# Spring2020.net
KiCad netlist of a schematic drawn in EAGLE
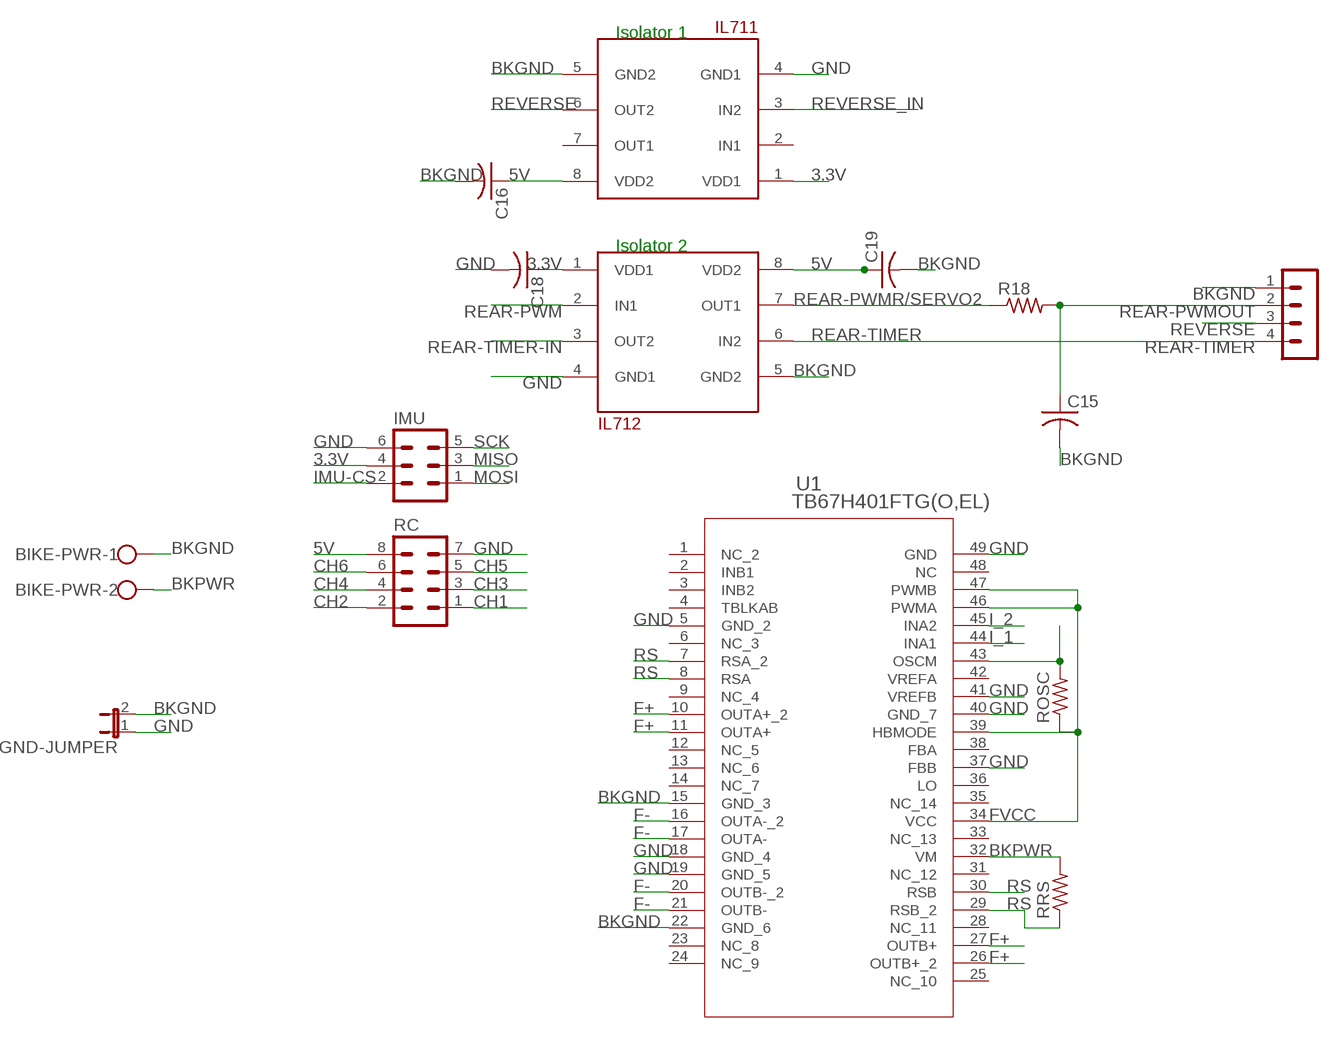
[diagram p0: schematic, sheet 1]

(export (version "E")
  (design (tool "Eeschema 10.0.6"))
  (components
    (comp (ref "BIKE-PWR")
      (value "W237-102")
      (footprint "eagle-import:W237-102")
      (fields (field (name "MPN") "237-102"))
      (libsource (lib "eagle-import") (part "W237-102"))
    )
    (comp (ref "C15")
      (value "C-US025-050X050")
      (footprint "eagle-import:C025-050X050")
      (libsource (lib "eagle-import") (part "C-US025-050X050"))
    )
    (comp (ref "C16")
      (value "C-US025-050X050")
      (footprint "eagle-import:C025-050X050")
      (libsource (lib "eagle-import") (part "C-US025-050X050"))
    )
    (comp (ref "C18")
      (value "C-US025-050X050")
      (footprint "eagle-import:C025-050X050")
      (libsource (lib "eagle-import") (part "C-US025-050X050"))
    )
    (comp (ref "C19")
      (value "C-US025-050X050")
      (footprint "eagle-import:C025-050X050")
      (libsource (lib "eagle-import") (part "C-US025-050X050"))
    )
    (comp (ref "GND-JUMPER")
      (value "JP1E")
      (footprint "eagle-import:JP1")
      (libsource (lib "eagle-import") (part "JP1E"))
    )
    (comp (ref "IMU")
      (value "MA03-2")
      (footprint "eagle-import:MA03-2")
      (libsource (lib "eagle-import") (part "MA03-2"))
    )
    (comp (ref "R18")
      (value "R-US_0414/15")
      (footprint "eagle-import:0414_15")
      (libsource (lib "eagle-import") (part "resistor_R-US_0414/15"))
    )
    (comp (ref "RC")
      (value "MA04-2")
      (footprint "eagle-import:MA04-2")
      (libsource (lib "eagle-import") (part "MA04-2"))
    )
    (comp (ref "REAR-MOTOR")
      (value "MA04-1")
      (footprint "eagle-import:MA04-1")
      (libsource (lib "eagle-import") (part "MA04-1"))
    )
    (comp (ref "ROSC")
      (value "R-US_0309/10")
      (footprint "eagle-import:0309_10")
      (libsource (lib "eagle-import") (part "R-US_0309/10"))
    )
    (comp (ref "RRS")
      (value "R-US_0309/10")
      (footprint "eagle-import:0309_10")
      (libsource (lib "eagle-import") (part "R-US_0309/10"))
    )
    (comp (ref "U$2")
      (value "IL-711")
      (footprint "eagle-import:8PINSOIC")
      (libsource (lib "eagle-import") (part "IL-711"))
    )
    (comp (ref "U$7")
      (value "IL-712")
      (footprint "eagle-import:8PINSOIC")
      (libsource (lib "eagle-import") (part "IL-712"))
    )
    (comp (ref "U1")
      (value "TB67H401FTG(O,EL)")
      (footprint "eagle-import:P-VQFN48-0707-0P50-004_TOS")
      (fields (field (name "COPYRIGHT") "Copyright (C) 2022 Ultra Librarian. All rights reserved."))
      (libsource (lib "eagle-import") (part "TB67H401FTG(O,EL)"))
    )
  )
  (nets
    (net (code "1") (name "/3.3V") (class "Default")
      (node (ref "C18") (pin "1") (pinfunction "1_1") (pintype "passive"))
      (node (ref "IMU") (pin "4") (pinfunction "4_4") (pintype "passive"))
      (node (ref "U$2") (pin "1") (pinfunction "VDD1_1") (pintype "power_in"))
      (node (ref "U$7") (pin "1") (pinfunction "VDD1_1") (pintype "power_in"))
    )
    (net (code "2") (name "/5V") (class "Default")
      (node (ref "C16") (pin "1") (pinfunction "1_1") (pintype "passive"))
      (node (ref "C19") (pin "1") (pinfunction "1_1") (pintype "passive"))
      (node (ref "RC") (pin "8") (pinfunction "8_8") (pintype "passive"))
      (node (ref "U$2") (pin "8") (pinfunction "VDD2_8") (pintype "power_in"))
      (node (ref "U$7") (pin "8") (pinfunction "VDD2_8") (pintype "power_in"))
    )
    (net (code "3") (name "/BKGND") (class "Default")
      (node (ref "BIKE-PWR") (pin "1") (pinfunction "KL_1") (pintype "passive"))
      (node (ref "C15") (pin "2") (pinfunction "2_2") (pintype "passive"))
      (node (ref "C16") (pin "2") (pinfunction "2_2") (pintype "passive"))
      (node (ref "C19") (pin "2") (pinfunction "2_2") (pintype "passive"))
      (node (ref "GND-JUMPER") (pin "2") (pinfunction "2_2") (pintype "passive"))
      (node (ref "REAR-MOTOR") (pin "1") (pinfunction "1_1") (pintype "passive"))
      (node (ref "U$2") (pin "5") (pinfunction "GND2_5") (pintype "power_in"))
      (node (ref "U$7") (pin "5") (pinfunction "GND2_5") (pintype "power_in"))
      (node (ref "U1") (pin "15") (pinfunction "GND_3_15") (pintype "passive"))
      (node (ref "U1") (pin "22") (pinfunction "GND_6_22") (pintype "passive"))
    )
    (net (code "4") (name "/BKPWR") (class "Default")
      (node (ref "BIKE-PWR") (pin "2") (pinfunction "KL_2") (pintype "passive"))
      (node (ref "RRS") (pin "2") (pinfunction "2_2") (pintype "passive"))
      (node (ref "U1") (pin "32") (pinfunction "VM_32") (pintype "passive"))
    )
    (net (code "5") (name "/CH1") (class "Default")
      (node (ref "RC") (pin "1") (pinfunction "1_1") (pintype "passive"))
    )
    (net (code "6") (name "/CH2") (class "Default")
      (node (ref "RC") (pin "2") (pinfunction "2_2") (pintype "passive"))
    )
    (net (code "7") (name "/CH3") (class "Default")
      (node (ref "RC") (pin "3") (pinfunction "3_3") (pintype "passive"))
    )
    (net (code "8") (name "/CH4") (class "Default")
      (node (ref "RC") (pin "4") (pinfunction "4_4") (pintype "passive"))
    )
    (net (code "9") (name "/CH5") (class "Default")
      (node (ref "RC") (pin "5") (pinfunction "5_5") (pintype "passive"))
    )
    (net (code "10") (name "/CH6") (class "Default")
      (node (ref "RC") (pin "6") (pinfunction "6_6") (pintype "passive"))
    )
    (net (code "11") (name "/F+") (class "Default")
      (node (ref "U1") (pin "10") (pinfunction "OUTA+_2_10") (pintype "output"))
      (node (ref "U1") (pin "11") (pinfunction "OUTA+_11") (pintype "output"))
      (node (ref "U1") (pin "26") (pinfunction "OUTB+_2_26") (pintype "output"))
      (node (ref "U1") (pin "27") (pinfunction "OUTB+_27") (pintype "output"))
    )
    (net (code "12") (name "/F-") (class "Default")
      (node (ref "U1") (pin "16") (pinfunction "OUTA-_2_16") (pintype "output"))
      (node (ref "U1") (pin "17") (pinfunction "OUTA-_17") (pintype "output"))
      (node (ref "U1") (pin "20") (pinfunction "OUTB-_2_20") (pintype "output"))
      (node (ref "U1") (pin "21") (pinfunction "OUTB-_21") (pintype "output"))
    )
    (net (code "13") (name "/FVCC") (class "Default")
      (node (ref "ROSC") (pin "1") (pinfunction "1_1") (pintype "passive"))
      (node (ref "U1") (pin "34") (pinfunction "VCC_34") (pintype "power_in"))
      (node (ref "U1") (pin "39") (pinfunction "HBMODE_39") (pintype "passive"))
      (node (ref "U1") (pin "46") (pinfunction "PWMA_46") (pintype "passive"))
      (node (ref "U1") (pin "47") (pinfunction "PWMB_47") (pintype "passive"))
    )
    (net (code "14") (name "/GND") (class "Default")
      (node (ref "C18") (pin "2") (pinfunction "2_2") (pintype "passive"))
      (node (ref "GND-JUMPER") (pin "1") (pinfunction "1_1") (pintype "passive"))
      (node (ref "IMU") (pin "6") (pinfunction "6_6") (pintype "passive"))
      (node (ref "RC") (pin "7") (pinfunction "7_7") (pintype "passive"))
      (node (ref "U$2") (pin "4") (pinfunction "GND1_4") (pintype "power_in"))
      (node (ref "U$7") (pin "4") (pinfunction "GND1_4") (pintype "power_in"))
      (node (ref "U1") (pin "18") (pinfunction "GND_4_18") (pintype "passive"))
      (node (ref "U1") (pin "19") (pinfunction "GND_5_19") (pintype "passive"))
      (node (ref "U1") (pin "37") (pinfunction "FBB_37") (pintype "passive"))
      (node (ref "U1") (pin "40") (pinfunction "GND_7_40") (pintype "passive"))
      (node (ref "U1") (pin "41") (pinfunction "VREFB_41") (pintype "power_in"))
      (node (ref "U1") (pin "49") (pinfunction "GND_49") (pintype "passive"))
      (node (ref "U1") (pin "5") (pinfunction "GND_2_5") (pintype "passive"))
    )
    (net (code "15") (name "/IMU-CS") (class "Default")
      (node (ref "IMU") (pin "2") (pinfunction "2_2") (pintype "passive"))
    )
    (net (code "16") (name "/I_1") (class "Default")
      (node (ref "U1") (pin "44") (pinfunction "INA1_44") (pintype "input"))
    )
    (net (code "17") (name "/I_2") (class "Default")
      (node (ref "U1") (pin "45") (pinfunction "INA2_45") (pintype "input"))
    )
    (net (code "18") (name "/MISO") (class "Default")
      (node (ref "IMU") (pin "3") (pinfunction "3_3") (pintype "passive"))
    )
    (net (code "19") (name "/MOSI") (class "Default")
      (node (ref "IMU") (pin "1") (pinfunction "1_1") (pintype "passive"))
    )
    (net (code "20") (name "/REAR-PWM") (class "Default")
      (node (ref "U$7") (pin "2") (pinfunction "IN1_2") (pintype "input"))
    )
    (net (code "21") (name "/REAR-PWMOUT") (class "Default")
      (node (ref "C15") (pin "1") (pinfunction "1_1") (pintype "passive"))
      (node (ref "R18") (pin "2") (pinfunction "2_2") (pintype "passive"))
      (node (ref "REAR-MOTOR") (pin "2") (pinfunction "2_2") (pintype "passive"))
    )
    (net (code "22") (name "/REAR-PWMR{slash}SERVO2") (class "Default")
      (node (ref "R18") (pin "1") (pinfunction "1_1") (pintype "passive"))
      (node (ref "U$7") (pin "7") (pinfunction "OUT1_7") (pintype "output"))
    )
    (net (code "23") (name "/REAR-TIMER") (class "Default")
      (node (ref "REAR-MOTOR") (pin "4") (pinfunction "4_4") (pintype "passive"))
      (node (ref "U$7") (pin "6") (pinfunction "IN2_6") (pintype "input"))
    )
    (net (code "24") (name "/REAR-TIMER-IN") (class "Default")
      (node (ref "U$7") (pin "3") (pinfunction "OUT2_3") (pintype "output"))
    )
    (net (code "25") (name "/REVERSE") (class "Default")
      (node (ref "REAR-MOTOR") (pin "3") (pinfunction "3_3") (pintype "passive"))
      (node (ref "U$2") (pin "6") (pinfunction "OUT2_6") (pintype "output"))
    )
    (net (code "26") (name "/REVERSE_IN") (class "Default")
      (node (ref "U$2") (pin "3") (pinfunction "IN2_3") (pintype "input"))
    )
    (net (code "27") (name "/RS") (class "Default")
      (node (ref "RRS") (pin "1") (pinfunction "1_1") (pintype "passive"))
      (node (ref "U1") (pin "29") (pinfunction "RSB_2_29") (pintype "passive"))
      (node (ref "U1") (pin "30") (pinfunction "RSB_30") (pintype "passive"))
      (node (ref "U1") (pin "7") (pinfunction "RSA_2_7") (pintype "passive"))
      (node (ref "U1") (pin "8") (pinfunction "RSA_8") (pintype "passive"))
    )
    (net (code "28") (name "/SCK") (class "Default")
      (node (ref "IMU") (pin "5") (pinfunction "5_5") (pintype "passive"))
    )
    (net (code "29") (name "/VREFA") (class "Default")
      (node (ref "U1") (pin "42") (pinfunction "VREFA_42") (pintype "power_in"))
    )
    (net (code "30") (name "Net-(U1-OSCM)") (class "Default")
      (node (ref "ROSC") (pin "2") (pinfunction "2_2") (pintype "passive"))
      (node (ref "U1") (pin "43") (pinfunction "OSCM_43") (pintype "passive"))
    )
    (net (code "31") (name "unconnected-(U$2-IN1-Pad2)") (class "Default")
      (node (ref "U$2") (pin "2") (pinfunction "IN1_2") (pintype "input"))
    )
    (net (code "32") (name "unconnected-(U$2-OUT1-Pad7)") (class "Default")
      (node (ref "U$2") (pin "7") (pinfunction "OUT1_7") (pintype "output"))
    )
    (net (code "33") (name "unconnected-(U1-FBA-Pad38)") (class "Default")
      (node (ref "U1") (pin "38") (pinfunction "FBA_38") (pintype "passive"))
    )
    (net (code "34") (name "unconnected-(U1-INB1-Pad2)") (class "Default")
      (node (ref "U1") (pin "2") (pinfunction "INB1_2") (pintype "input"))
    )
    (net (code "35") (name "unconnected-(U1-INB2-Pad3)") (class "Default")
      (node (ref "U1") (pin "3") (pinfunction "INB2_3") (pintype "input"))
    )
    (net (code "36") (name "unconnected-(U1-LO-Pad36)") (class "Default")
      (node (ref "U1") (pin "36") (pinfunction "LO_36") (pintype "passive"))
    )
    (net (code "37") (name "unconnected-(U1-NC-Pad48)") (class "Default")
      (node (ref "U1") (pin "48") (pinfunction "NC_48") (pintype "no_connect"))
    )
    (net (code "38") (name "unconnected-(U1-NC_2-Pad1)") (class "Default")
      (node (ref "U1") (pin "1") (pinfunction "NC_2_1") (pintype "no_connect"))
    )
    (net (code "39") (name "unconnected-(U1-NC_3-Pad6)") (class "Default")
      (node (ref "U1") (pin "6") (pinfunction "NC_3_6") (pintype "no_connect"))
    )
    (net (code "40") (name "unconnected-(U1-NC_4-Pad9)") (class "Default")
      (node (ref "U1") (pin "9") (pinfunction "NC_4_9") (pintype "no_connect"))
    )
    (net (code "41") (name "unconnected-(U1-NC_5-Pad12)") (class "Default")
      (node (ref "U1") (pin "12") (pinfunction "NC_5_12") (pintype "no_connect"))
    )
    (net (code "42") (name "unconnected-(U1-NC_6-Pad13)") (class "Default")
      (node (ref "U1") (pin "13") (pinfunction "NC_6_13") (pintype "no_connect"))
    )
    (net (code "43") (name "unconnected-(U1-NC_7-Pad14)") (class "Default")
      (node (ref "U1") (pin "14") (pinfunction "NC_7_14") (pintype "no_connect"))
    )
    (net (code "44") (name "unconnected-(U1-NC_8-Pad23)") (class "Default")
      (node (ref "U1") (pin "23") (pinfunction "NC_8_23") (pintype "no_connect"))
    )
    (net (code "45") (name "unconnected-(U1-NC_9-Pad24)") (class "Default")
      (node (ref "U1") (pin "24") (pinfunction "NC_9_24") (pintype "no_connect"))
    )
    (net (code "46") (name "unconnected-(U1-NC_10-Pad25)") (class "Default")
      (node (ref "U1") (pin "25") (pinfunction "NC_10_25") (pintype "no_connect"))
    )
    (net (code "47") (name "unconnected-(U1-NC_11-Pad28)") (class "Default")
      (node (ref "U1") (pin "28") (pinfunction "NC_11_28") (pintype "no_connect"))
    )
    (net (code "48") (name "unconnected-(U1-NC_12-Pad31)") (class "Default")
      (node (ref "U1") (pin "31") (pinfunction "NC_12_31") (pintype "no_connect"))
    )
    (net (code "49") (name "unconnected-(U1-NC_13-Pad33)") (class "Default")
      (node (ref "U1") (pin "33") (pinfunction "NC_13_33") (pintype "no_connect"))
    )
    (net (code "50") (name "unconnected-(U1-NC_14-Pad35)") (class "Default")
      (node (ref "U1") (pin "35") (pinfunction "NC_14_35") (pintype "no_connect"))
    )
    (net (code "51") (name "unconnected-(U1-TBLKAB-Pad4)") (class "Default")
      (node (ref "U1") (pin "4") (pinfunction "TBLKAB_4") (pintype "passive"))
    )
  )
)
